# Qwiic-Power-Switch.net
KiCad netlist of a schematic drawn in EAGLE
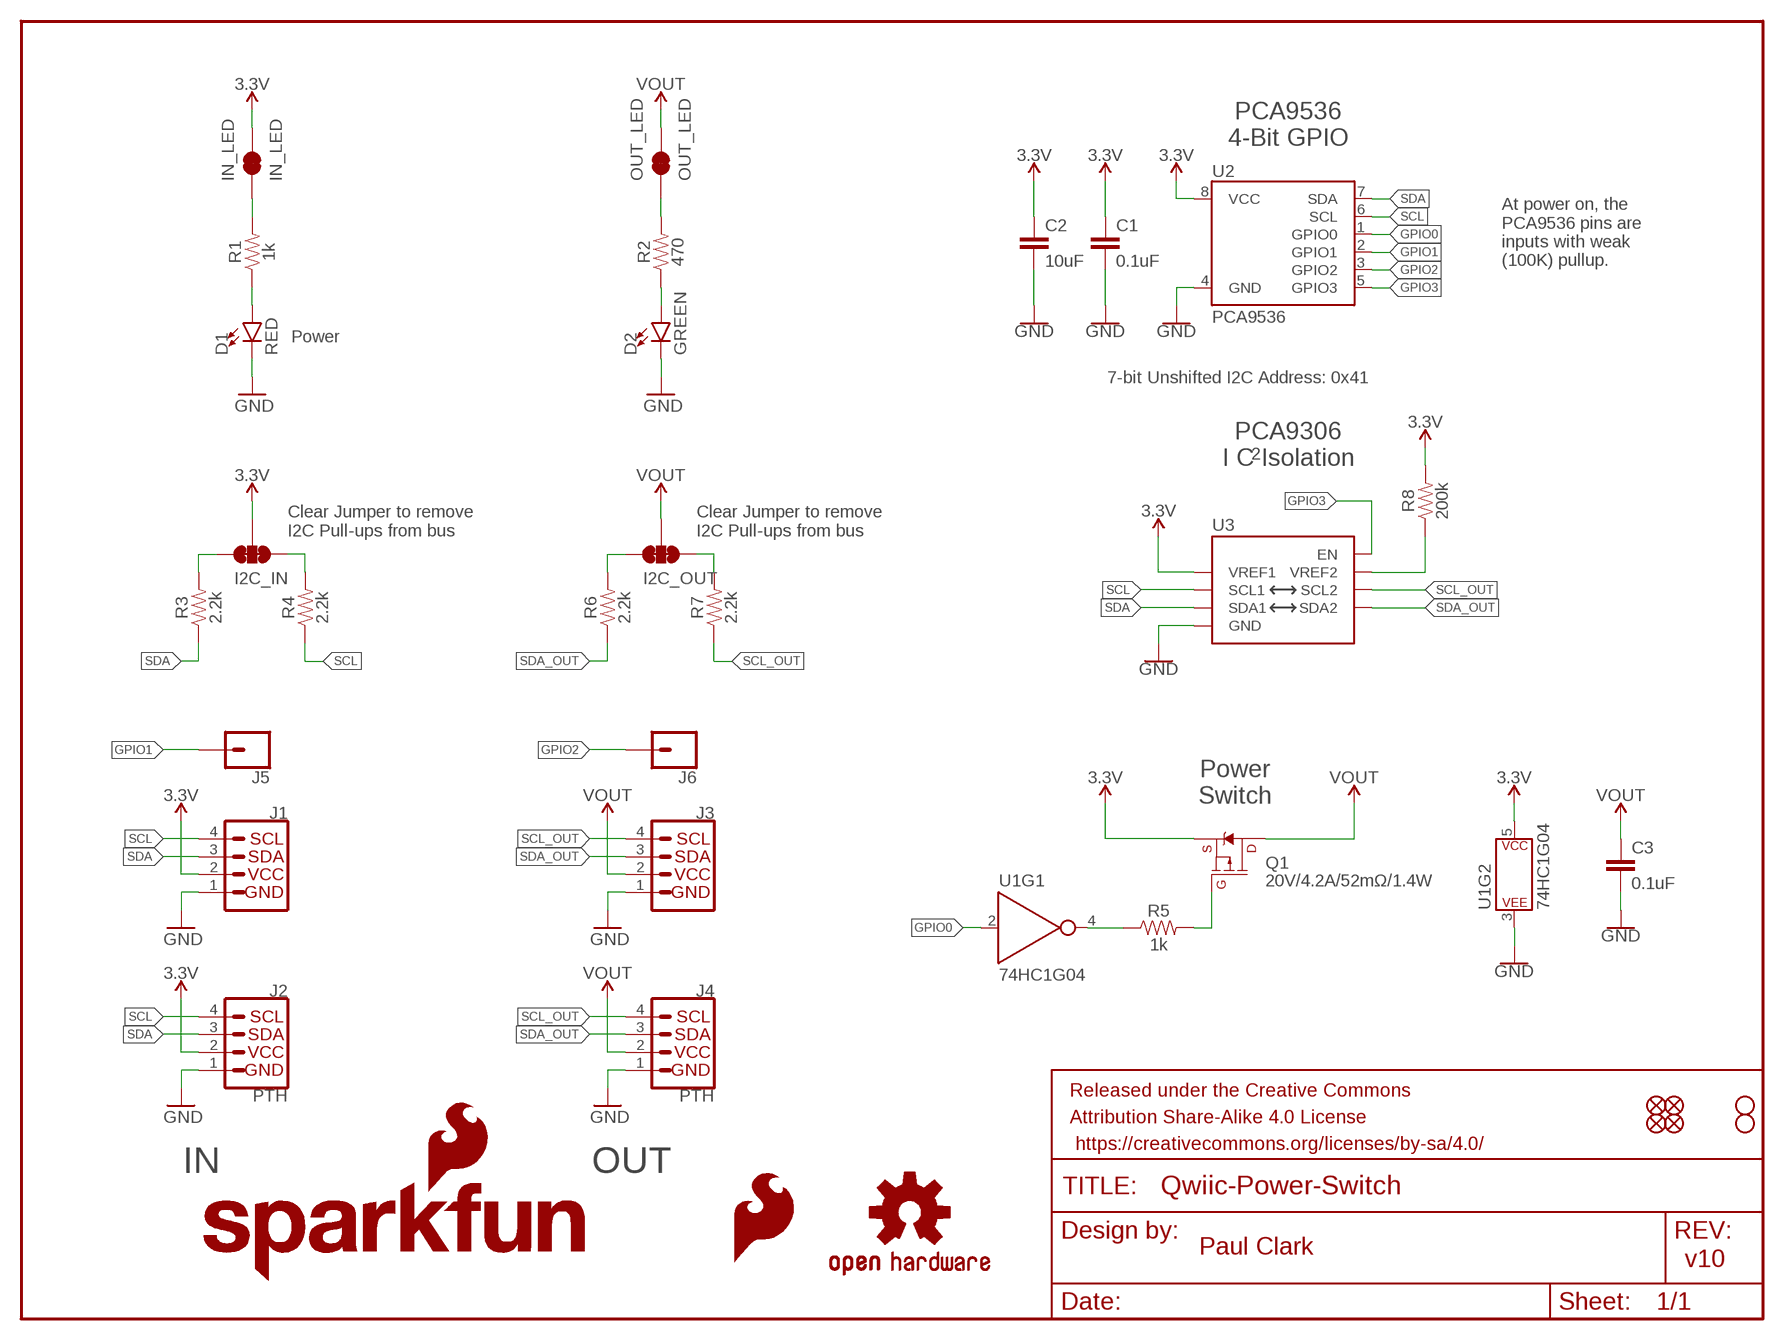
[diagram p0: schematic, sheet 1]

(export (version "E")
  (design (tool "Eeschema 10.0.6"))
  (components
    (comp (ref "C1")
      (value "0.1uF")
      (footprint "eagle-import:0603")
      (libsource (lib "eagle-import") (part "0.1UF-0603-25V-(+80/-20%)"))
    )
    (comp (ref "C2")
      (value "10uF")
      (footprint "eagle-import:0603")
      (libsource (lib "eagle-import") (part "10UF-0603-6.3V-20%"))
    )
    (comp (ref "C3")
      (value "0.1uF")
      (footprint "eagle-import:0603")
      (libsource (lib "eagle-import") (part "0.1UF-0603-25V-(+80/-20%)"))
    )
    (comp (ref "D1")
      (value "RED")
      (footprint "eagle-import:LED-0603")
      (libsource (lib "eagle-import") (part "LED-RED0603"))
    )
    (comp (ref "D2")
      (value "GREEN")
      (footprint "eagle-import:LED-0603")
      (libsource (lib "eagle-import") (part "LED-GREEN0603"))
    )
    (comp (ref "FRAME1")
      (value "FRAME-LETTER")
      (footprint "eagle-import:CREATIVE_COMMONS")
      (libsource (lib "eagle-import") (part "FRAME-LETTER"))
    )
    (comp (ref "I2C_IN")
      (value "JUMPER-SMT_3_2-NC_TRACE_SILK")
      (footprint "eagle-import:SMT-JUMPER_3_2-NC_TRACE_SILK")
      (libsource (lib "eagle-import") (part "JUMPER-SMT_3_2-NC_TRACE_SILK"))
    )
    (comp (ref "I2C_OUT")
      (value "JUMPER-SMT_3_2-NC_TRACE_SILK")
      (footprint "eagle-import:SMT-JUMPER_3_2-NC_TRACE_SILK")
      (libsource (lib "eagle-import") (part "JUMPER-SMT_3_2-NC_TRACE_SILK"))
    )
    (comp (ref "IN_LED")
      (value "IN_LED")
      (footprint "eagle-import:SMT-JUMPER_2_NC_TRACE_SILK")
      (libsource (lib "eagle-import") (part "JUMPER-SMT_2_NC_TRACE_SILK"))
    )
    (comp (ref "J1")
      (value "Qwiic Right Angle")
      (footprint "eagle-import:JST04_1MM_RA")
      (libsource (lib "eagle-import") (part "I2C_STANDARDQWIIC"))
    )
    (comp (ref "J2")
      (value "PTH")
      (footprint "eagle-import:1X04_NO_SILK")
      (libsource (lib "eagle-import") (part "I2C_STANDARD_NO_SILK"))
    )
    (comp (ref "J3")
      (value "Qwiic Right Angle")
      (footprint "eagle-import:JST04_1MM_RA")
      (libsource (lib "eagle-import") (part "I2C_STANDARDQWIIC"))
    )
    (comp (ref "J4")
      (value "PTH")
      (footprint "eagle-import:1X04_NO_SILK")
      (libsource (lib "eagle-import") (part "I2C_STANDARD_NO_SILK"))
    )
    (comp (ref "J5")
      (value "CONN_01PTH_NO_SILK_YES_STOP")
      (footprint "eagle-import:1X01_NO_SILK")
      (libsource (lib "eagle-import") (part "CONN_01PTH_NO_SILK_YES_STOP"))
    )
    (comp (ref "J6")
      (value "CONN_01PTH_NO_SILK_YES_STOP")
      (footprint "eagle-import:1X01_NO_SILK")
      (libsource (lib "eagle-import") (part "CONN_01PTH_NO_SILK_YES_STOP"))
    )
    (comp (ref "JP1")
      (value "FIDUCIAL1X2")
      (footprint "eagle-import:FIDUCIAL-1X2")
      (libsource (lib "eagle-import") (part "FIDUCIAL1X2"))
    )
    (comp (ref "JP2")
      (value "FIDUCIAL1X2")
      (footprint "eagle-import:FIDUCIAL-1X2")
      (libsource (lib "eagle-import") (part "FIDUCIAL1X2"))
    )
    (comp (ref "JP3")
      (value "STAND-OFF")
      (footprint "eagle-import:STAND-OFF")
      (libsource (lib "eagle-import") (part "STAND-OFF"))
    )
    (comp (ref "JP4")
      (value "STAND-OFF")
      (footprint "eagle-import:STAND-OFF")
      (libsource (lib "eagle-import") (part "STAND-OFF"))
    )
    (comp (ref "JP5")
      (value "FIDUCIAL1X2")
      (footprint "eagle-import:FIDUCIAL-1X2")
      (libsource (lib "eagle-import") (part "FIDUCIAL1X2"))
    )
    (comp (ref "JP6")
      (value "FIDUCIAL1X2")
      (footprint "eagle-import:FIDUCIAL-1X2")
      (libsource (lib "eagle-import") (part "FIDUCIAL1X2"))
    )
    (comp (ref "LOGO1")
      (value "OSHW-LOGOMINI")
      (footprint "eagle-import:OSHW-LOGO-MINI")
      (libsource (lib "eagle-import") (part "OSHW-LOGOMINI"))
    )
    (comp (ref "LOGO2")
      (value "SFE_LOGO_FLAME.1_INCH")
      (footprint "eagle-import:SFE_LOGO_FLAME_.1")
      (libsource (lib "eagle-import") (part "SFE_LOGO_FLAME.1_INCH"))
    )
    (comp (ref "LOGO3")
      (value "SFE_LOGO_NAME_FLAME.1_INCH")
      (footprint "eagle-import:SFE_LOGO_NAME_FLAME_.1")
      (libsource (lib "eagle-import") (part "SFE_LOGO_NAME_FLAME.1_INCH"))
    )
    (comp (ref "OUT_LED")
      (value "OUT_LED")
      (footprint "eagle-import:SMT-JUMPER_2_NC_TRACE_SILK")
      (libsource (lib "eagle-import") (part "JUMPER-SMT_2_NC_TRACE_SILK"))
    )
    (comp (ref "Q1")
      (value "20V/4.2A/52mΩ/1.4W")
      (footprint "eagle-import:SOT23-3")
      (libsource (lib "eagle-import") (part "MOSFET_PCH-DMG2305UX-7"))
    )
    (comp (ref "R1")
      (value "1k")
      (footprint "eagle-import:0603")
      (libsource (lib "eagle-import") (part "1KOHM-0603-1/10W-1%"))
    )
    (comp (ref "R2")
      (value "470")
      (footprint "eagle-import:0603")
      (libsource (lib "eagle-import") (part "470OHM-0603-1/10W-1%"))
    )
    (comp (ref "R3")
      (value "2.2k")
      (footprint "eagle-import:0603")
      (libsource (lib "eagle-import") (part "2.2KOHM-0603-1/10W-1%"))
    )
    (comp (ref "R4")
      (value "2.2k")
      (footprint "eagle-import:0603")
      (libsource (lib "eagle-import") (part "2.2KOHM-0603-1/10W-1%"))
    )
    (comp (ref "R5")
      (value "1k")
      (footprint "eagle-import:0603")
      (libsource (lib "eagle-import") (part "1KOHM-0603-1/10W-1%"))
    )
    (comp (ref "R6")
      (value "2.2k")
      (footprint "eagle-import:0603")
      (libsource (lib "eagle-import") (part "2.2KOHM-0603-1/10W-1%"))
    )
    (comp (ref "R7")
      (value "2.2k")
      (footprint "eagle-import:0603")
      (libsource (lib "eagle-import") (part "2.2KOHM-0603-1/10W-1%"))
    )
    (comp (ref "R8")
      (value "200k")
      (footprint "eagle-import:0603")
      (libsource (lib "eagle-import") (part "200KOHM-0603-1/10W-1%"))
    )
    (comp (ref "U1")
      (value "74HC1G04")
      (footprint "eagle-import:SOT353")
      (libsource (lib "eagle-import") (part "741G04HC"))
    )
    (comp (ref "U2")
      (value "PCA9536")
      (footprint "eagle-import:MSOP8")
      (libsource (lib "eagle-import") (part "PCA9536"))
    )
    (comp (ref "U3")
      (value "PCA9306VSSOP_8PIN")
      (footprint "eagle-import:VSSOP_8PIN")
      (libsource (lib "eagle-import") (part "PCA9306VSSOP_8PIN"))
    )
  )
  (nets
    (net (code "1") (name "3.3V") (class "Default")
      (node (ref "C1") (pin "1") (pinfunction "1_1") (pintype "passive"))
      (node (ref "C2") (pin "1") (pinfunction "1_1") (pintype "passive"))
      (node (ref "I2C_IN") (pin "2") (pinfunction "2_2") (pintype "passive"))
      (node (ref "IN_LED") (pin "2") (pinfunction "2_2") (pintype "passive"))
      (node (ref "J1") (pin "2") (pinfunction "2_2") (pintype "power_in"))
      (node (ref "J2") (pin "2") (pinfunction "2_2") (pintype "power_in"))
      (node (ref "Q1") (pin "2") (pinfunction "S_2") (pintype "bidirectional"))
      (node (ref "R8") (pin "2") (pinfunction "2_2") (pintype "passive"))
      (node (ref "U1") (pin "5") (pinfunction "P$V+_5") (pintype "bidirectional"))
      (node (ref "U2") (pin "8") (pinfunction "VCC_8") (pintype "bidirectional"))
      (node (ref "U3") (pin "P2") (pinfunction "VREF1_P2") (pintype "power_in"))
    )
    (net (code "2") (name "GND") (class "Default")
      (node (ref "C1") (pin "2") (pinfunction "2_2") (pintype "passive"))
      (node (ref "C2") (pin "2") (pinfunction "2_2") (pintype "passive"))
      (node (ref "C3") (pin "2") (pinfunction "2_2") (pintype "passive"))
      (node (ref "D1") (pin "C") (pinfunction "C_C") (pintype "passive"))
      (node (ref "D2") (pin "C") (pinfunction "C_C") (pintype "passive"))
      (node (ref "J1") (pin "1") (pinfunction "1_1") (pintype "power_in"))
      (node (ref "J2") (pin "1") (pinfunction "1_1") (pintype "power_in"))
      (node (ref "J3") (pin "1") (pinfunction "1_1") (pintype "power_in"))
      (node (ref "J4") (pin "1") (pinfunction "1_1") (pintype "power_in"))
      (node (ref "U1") (pin "3") (pinfunction "P$V-_3") (pintype "bidirectional"))
      (node (ref "U2") (pin "4") (pinfunction "GND_4") (pintype "bidirectional"))
      (node (ref "U3") (pin "P1") (pinfunction "GND_P1") (pintype "power_in"))
    )
    (net (code "3") (name "GPIO0") (class "Default")
      (node (ref "U1") (pin "2") (pinfunction "A_2") (pintype "bidirectional"))
      (node (ref "U2") (pin "1") (pinfunction "GPIO0_1") (pintype "bidirectional"))
    )
    (net (code "4") (name "GPIO1") (class "Default")
      (node (ref "J5") (pin "1") (pinfunction "1_1") (pintype "passive"))
      (node (ref "U2") (pin "2") (pinfunction "GPIO1_2") (pintype "bidirectional"))
    )
    (net (code "5") (name "GPIO2") (class "Default")
      (node (ref "J6") (pin "1") (pinfunction "1_1") (pintype "passive"))
      (node (ref "U2") (pin "3") (pinfunction "GPIO2_3") (pintype "bidirectional"))
    )
    (net (code "6") (name "GPIO3") (class "Default")
      (node (ref "U2") (pin "5") (pinfunction "GPIO3_5") (pintype "bidirectional"))
      (node (ref "U3") (pin "P8") (pinfunction "EN_P8") (pintype "input"))
    )
    (net (code "7") (name "Net-(D1-PadA)") (class "Default")
      (node (ref "D1") (pin "A") (pinfunction "A_A") (pintype "passive"))
      (node (ref "R1") (pin "1") (pinfunction "1_1") (pintype "passive"))
    )
    (net (code "8") (name "Net-(D2-PadA)") (class "Default")
      (node (ref "D2") (pin "A") (pinfunction "A_A") (pintype "passive"))
      (node (ref "R2") (pin "1") (pinfunction "1_1") (pintype "passive"))
    )
    (net (code "9") (name "Net-(I2C_IN-Pad1)") (class "Default")
      (node (ref "I2C_IN") (pin "1") (pinfunction "1_1") (pintype "passive"))
      (node (ref "R4") (pin "2") (pinfunction "2_2") (pintype "passive"))
    )
    (net (code "10") (name "Net-(I2C_IN-Pad3)") (class "Default")
      (node (ref "I2C_IN") (pin "3") (pinfunction "3_3") (pintype "passive"))
      (node (ref "R3") (pin "2") (pinfunction "2_2") (pintype "passive"))
    )
    (net (code "11") (name "Net-(I2C_OUT-Pad1)") (class "Default")
      (node (ref "I2C_OUT") (pin "1") (pinfunction "1_1") (pintype "passive"))
      (node (ref "R7") (pin "2") (pinfunction "2_2") (pintype "passive"))
    )
    (net (code "12") (name "Net-(I2C_OUT-Pad3)") (class "Default")
      (node (ref "I2C_OUT") (pin "3") (pinfunction "3_3") (pintype "passive"))
      (node (ref "R6") (pin "2") (pinfunction "2_2") (pintype "passive"))
    )
    (net (code "13") (name "Net-(IN_LED-Pad1)") (class "Default")
      (node (ref "IN_LED") (pin "1") (pinfunction "1_1") (pintype "passive"))
      (node (ref "R1") (pin "2") (pinfunction "2_2") (pintype "passive"))
    )
    (net (code "14") (name "Net-(OUT_LED-Pad1)") (class "Default")
      (node (ref "OUT_LED") (pin "1") (pinfunction "1_1") (pintype "passive"))
      (node (ref "R2") (pin "2") (pinfunction "2_2") (pintype "passive"))
    )
    (net (code "15") (name "Net-(Q1-G)") (class "Default")
      (node (ref "Q1") (pin "1") (pinfunction "G_1") (pintype "bidirectional"))
      (node (ref "R5") (pin "2") (pinfunction "2_2") (pintype "passive"))
    )
    (net (code "16") (name "Net-(U1A-Y)") (class "Default")
      (node (ref "R5") (pin "1") (pinfunction "1_1") (pintype "passive"))
      (node (ref "U1") (pin "4") (pinfunction "Y_4") (pintype "bidirectional"))
    )
    (net (code "17") (name "Net-(U3-VREF2)") (class "Default")
      (node (ref "R8") (pin "1") (pinfunction "1_1") (pintype "passive"))
      (node (ref "U3") (pin "P7") (pinfunction "VREF2_P7") (pintype "power_in"))
    )
    (net (code "18") (name "SCL") (class "Default")
      (node (ref "J1") (pin "4") (pinfunction "4_4") (pintype "passive"))
      (node (ref "J2") (pin "4") (pinfunction "4_4") (pintype "passive"))
      (node (ref "R4") (pin "1") (pinfunction "1_1") (pintype "passive"))
      (node (ref "U2") (pin "6") (pinfunction "SCL_6") (pintype "bidirectional"))
      (node (ref "U3") (pin "P3") (pinfunction "SCL1_P3") (pintype "bidirectional"))
    )
    (net (code "19") (name "SCL_OUT") (class "Default")
      (node (ref "J3") (pin "4") (pinfunction "4_4") (pintype "passive"))
      (node (ref "J4") (pin "4") (pinfunction "4_4") (pintype "passive"))
      (node (ref "R7") (pin "1") (pinfunction "1_1") (pintype "passive"))
      (node (ref "U3") (pin "P6") (pinfunction "SCL2_P6") (pintype "bidirectional"))
    )
    (net (code "20") (name "SDA") (class "Default")
      (node (ref "J1") (pin "3") (pinfunction "3_3") (pintype "passive"))
      (node (ref "J2") (pin "3") (pinfunction "3_3") (pintype "passive"))
      (node (ref "R3") (pin "1") (pinfunction "1_1") (pintype "passive"))
      (node (ref "U2") (pin "7") (pinfunction "SDA_7") (pintype "bidirectional"))
      (node (ref "U3") (pin "P4") (pinfunction "SDA1_P4") (pintype "bidirectional"))
    )
    (net (code "21") (name "SDA_OUT") (class "Default")
      (node (ref "J3") (pin "3") (pinfunction "3_3") (pintype "passive"))
      (node (ref "J4") (pin "3") (pinfunction "3_3") (pintype "passive"))
      (node (ref "R6") (pin "1") (pinfunction "1_1") (pintype "passive"))
      (node (ref "U3") (pin "P5") (pinfunction "SDA2_P5") (pintype "bidirectional"))
    )
    (net (code "22") (name "VOUT") (class "Default")
      (node (ref "C3") (pin "1") (pinfunction "1_1") (pintype "passive"))
      (node (ref "I2C_OUT") (pin "2") (pinfunction "2_2") (pintype "passive"))
      (node (ref "J3") (pin "2") (pinfunction "2_2") (pintype "power_in"))
      (node (ref "J4") (pin "2") (pinfunction "2_2") (pintype "power_in"))
      (node (ref "OUT_LED") (pin "2") (pinfunction "2_2") (pintype "passive"))
      (node (ref "Q1") (pin "3") (pinfunction "D_3") (pintype "bidirectional"))
    )
  )
)
